# final_coard.net
KiCad netlist of a schematic drawn in EAGLE
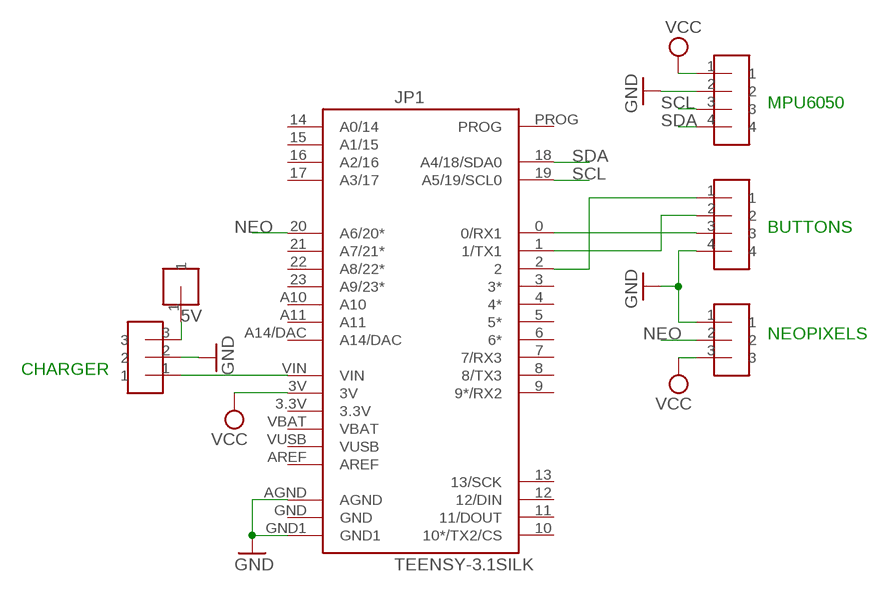
[diagram p0: schematic, sheet 1]

(export (version "E")
  (design (tool "Eeschema 10.0.6"))
  (components
    (comp (ref "JP1")
      (value "TEENSY-3.1SILK")
      (footprint "eagle-import:TEENSY-3.1")
      (libsource (lib "eagle-import") (part "TEENSY-3.1SILK"))
    )
    (comp (ref "U$1")
      (value "HEADER-3")
      (footprint "eagle-import:HEADER-3")
      (libsource (lib "eagle-import") (part "HEADER-3"))
    )
    (comp (ref "U$2")
      (value "HEADER-3")
      (footprint "eagle-import:HEADER-3")
      (libsource (lib "eagle-import") (part "HEADER-3"))
    )
    (comp (ref "U$3")
      (value "HEADER-1")
      (footprint "eagle-import:HEADER-1")
      (libsource (lib "eagle-import") (part "HEADER-1"))
    )
    (comp (ref "U$4")
      (value "HEADER-4")
      (footprint "eagle-import:HEADER-4")
      (libsource (lib "eagle-import") (part "HEADER-4"))
    )
    (comp (ref "U$5")
      (value "HEADER-4")
      (footprint "eagle-import:HEADER-4")
      (libsource (lib "eagle-import") (part "HEADER-4"))
    )
  )
  (nets
    (net (code "1") (name "/5V") (class "Default")
      (node (ref "U$1") (pin "3") (pinfunction "3_3") (pintype "bidirectional"))
      (node (ref "U$3") (pin "1") (pinfunction "1_1") (pintype "bidirectional"))
    )
    (net (code "2") (name "/NEO") (class "Default")
      (node (ref "JP1") (pin "20") (pinfunction "A6/20*_20") (pintype "bidirectional"))
      (node (ref "U$2") (pin "2") (pinfunction "2_2") (pintype "bidirectional"))
    )
    (net (code "3") (name "/SCL") (class "Default")
      (node (ref "JP1") (pin "19") (pinfunction "A5/19/SCL0_19") (pintype "bidirectional"))
      (node (ref "U$4") (pin "3") (pinfunction "3_3") (pintype "bidirectional"))
    )
    (net (code "4") (name "/SDA") (class "Default")
      (node (ref "JP1") (pin "18") (pinfunction "A4/18/SDA0_18") (pintype "bidirectional"))
      (node (ref "U$4") (pin "4") (pinfunction "4_4") (pintype "bidirectional"))
    )
    (net (code "5") (name "GND") (class "Default")
      (node (ref "JP1") (pin "AGND") (pinfunction "AGND_AGND") (pintype "bidirectional"))
      (node (ref "JP1") (pin "GND1") (pinfunction "GND1_GND1") (pintype "bidirectional"))
      (node (ref "U$1") (pin "2") (pinfunction "2_2") (pintype "bidirectional"))
      (node (ref "U$2") (pin "1") (pinfunction "1_1") (pintype "bidirectional"))
      (node (ref "U$4") (pin "2") (pinfunction "2_2") (pintype "bidirectional"))
      (node (ref "U$5") (pin "4") (pinfunction "4_4") (pintype "bidirectional"))
    )
    (net (code "6") (name "Net-(JP1-0{slash}RX1)") (class "Default")
      (node (ref "JP1") (pin "0") (pinfunction "0/RX1_0") (pintype "bidirectional"))
      (node (ref "U$5") (pin "3") (pinfunction "3_3") (pintype "bidirectional"))
    )
    (net (code "7") (name "Net-(JP1-1{slash}TX1)") (class "Default")
      (node (ref "JP1") (pin "1") (pinfunction "1/TX1_1") (pintype "bidirectional"))
      (node (ref "U$5") (pin "2") (pinfunction "2_2") (pintype "bidirectional"))
    )
    (net (code "8") (name "Net-(JP1-Pad2)") (class "Default")
      (node (ref "JP1") (pin "2") (pinfunction "2_2") (pintype "bidirectional"))
      (node (ref "U$5") (pin "1") (pinfunction "1_1") (pintype "bidirectional"))
    )
    (net (code "9") (name "Net-(JP1-PadVIN)") (class "Default")
      (node (ref "JP1") (pin "VIN") (pinfunction "VIN_VIN") (pintype "bidirectional"))
      (node (ref "U$1") (pin "1") (pinfunction "1_1") (pintype "bidirectional"))
    )
    (net (code "10") (name "VCC") (class "Default")
      (node (ref "JP1") (pin "3V") (pinfunction "3V_3V") (pintype "bidirectional"))
      (node (ref "U$2") (pin "3") (pinfunction "3_3") (pintype "bidirectional"))
      (node (ref "U$4") (pin "1") (pinfunction "1_1") (pintype "bidirectional"))
    )
    (net (code "11") (name "unconnected-(JP1-3*-Pad3)") (class "Default")
      (node (ref "JP1") (pin "3") (pinfunction "3*_3") (pintype "bidirectional"))
    )
    (net (code "12") (name "unconnected-(JP1-4*-Pad4)") (class "Default")
      (node (ref "JP1") (pin "4") (pinfunction "4*_4") (pintype "bidirectional"))
    )
    (net (code "13") (name "unconnected-(JP1-5*-Pad5)") (class "Default")
      (node (ref "JP1") (pin "5") (pinfunction "5*_5") (pintype "bidirectional"))
    )
    (net (code "14") (name "unconnected-(JP1-6*-Pad6)") (class "Default")
      (node (ref "JP1") (pin "6") (pinfunction "6*_6") (pintype "bidirectional"))
    )
    (net (code "15") (name "unconnected-(JP1-7{slash}RX3-Pad7)") (class "Default")
      (node (ref "JP1") (pin "7") (pinfunction "7/RX3_7") (pintype "bidirectional"))
    )
    (net (code "16") (name "unconnected-(JP1-8{slash}TX3-Pad8)") (class "Default")
      (node (ref "JP1") (pin "8") (pinfunction "8/TX3_8") (pintype "bidirectional"))
    )
    (net (code "17") (name "unconnected-(JP1-9*{slash}RX2-Pad9)") (class "Default")
      (node (ref "JP1") (pin "9") (pinfunction "9*/RX2_9") (pintype "bidirectional"))
    )
    (net (code "18") (name "unconnected-(JP1-10*{slash}TX2{slash}CS-Pad10)") (class "Default")
      (node (ref "JP1") (pin "10") (pinfunction "10*/TX2/CS_10") (pintype "bidirectional"))
    )
    (net (code "19") (name "unconnected-(JP1-11{slash}DOUT-Pad11)") (class "Default")
      (node (ref "JP1") (pin "11") (pinfunction "11/DOUT_11") (pintype "bidirectional"))
    )
    (net (code "20") (name "unconnected-(JP1-12{slash}DIN-Pad12)") (class "Default")
      (node (ref "JP1") (pin "12") (pinfunction "12/DIN_12") (pintype "bidirectional"))
    )
    (net (code "21") (name "unconnected-(JP1-13{slash}SCK-Pad13)") (class "Default")
      (node (ref "JP1") (pin "13") (pinfunction "13/SCK_13") (pintype "bidirectional"))
    )
    (net (code "22") (name "unconnected-(JP1-A0{slash}14-Pad14)") (class "Default")
      (node (ref "JP1") (pin "14") (pinfunction "A0/14_14") (pintype "bidirectional"))
    )
    (net (code "23") (name "unconnected-(JP1-A1{slash}15-Pad15)") (class "Default")
      (node (ref "JP1") (pin "15") (pinfunction "A1/15_15") (pintype "bidirectional"))
    )
    (net (code "24") (name "unconnected-(JP1-A2{slash}16-Pad16)") (class "Default")
      (node (ref "JP1") (pin "16") (pinfunction "A2/16_16") (pintype "bidirectional"))
    )
    (net (code "25") (name "unconnected-(JP1-A3{slash}17-Pad17)") (class "Default")
      (node (ref "JP1") (pin "17") (pinfunction "A3/17_17") (pintype "bidirectional"))
    )
    (net (code "26") (name "unconnected-(JP1-A7{slash}21*-Pad21)") (class "Default")
      (node (ref "JP1") (pin "21") (pinfunction "A7/21*_21") (pintype "bidirectional"))
    )
    (net (code "27") (name "unconnected-(JP1-A8{slash}22*-Pad22)") (class "Default")
      (node (ref "JP1") (pin "22") (pinfunction "A8/22*_22") (pintype "bidirectional"))
    )
    (net (code "28") (name "unconnected-(JP1-A9{slash}23*-Pad23)") (class "Default")
      (node (ref "JP1") (pin "23") (pinfunction "A9/23*_23") (pintype "bidirectional"))
    )
    (net (code "29") (name "unconnected-(JP1-Pad3.3V)") (class "Default")
      (node (ref "JP1") (pin "3.3V") (pinfunction "3.3V_3.3V") (pintype "bidirectional"))
    )
    (net (code "30") (name "unconnected-(JP1-PadA10)") (class "Default")
      (node (ref "JP1") (pin "A10") (pinfunction "A10_A10") (pintype "bidirectional"))
    )
    (net (code "31") (name "unconnected-(JP1-PadA11)") (class "Default")
      (node (ref "JP1") (pin "A11") (pinfunction "A11_A11") (pintype "bidirectional"))
    )
    (net (code "32") (name "unconnected-(JP1-PadA14{slash}DAC)") (class "Default")
      (node (ref "JP1") (pin "A14/DAC") (pinfunction "A14/DAC_A14/DAC") (pintype "bidirectional"))
    )
    (net (code "33") (name "unconnected-(JP1-PadAREF)") (class "Default")
      (node (ref "JP1") (pin "AREF") (pinfunction "AREF_AREF") (pintype "bidirectional"))
    )
    (net (code "34") (name "unconnected-(JP1-PadGND)") (class "Default")
      (node (ref "JP1") (pin "GND") (pinfunction "GND_GND") (pintype "bidirectional"))
    )
    (net (code "35") (name "unconnected-(JP1-PadPROG)") (class "Default")
      (node (ref "JP1") (pin "PROG") (pinfunction "PROG_PROG") (pintype "bidirectional"))
    )
    (net (code "36") (name "unconnected-(JP1-PadVBAT)") (class "Default")
      (node (ref "JP1") (pin "VBAT") (pinfunction "VBAT_VBAT") (pintype "bidirectional"))
    )
    (net (code "37") (name "unconnected-(JP1-PadVUSB)") (class "Default")
      (node (ref "JP1") (pin "VUSB") (pinfunction "VUSB_VUSB") (pintype "bidirectional"))
    )
  )
)
